# IrDA2TTLBoard.net
KiCad netlist of a schematic drawn in Altium Designer
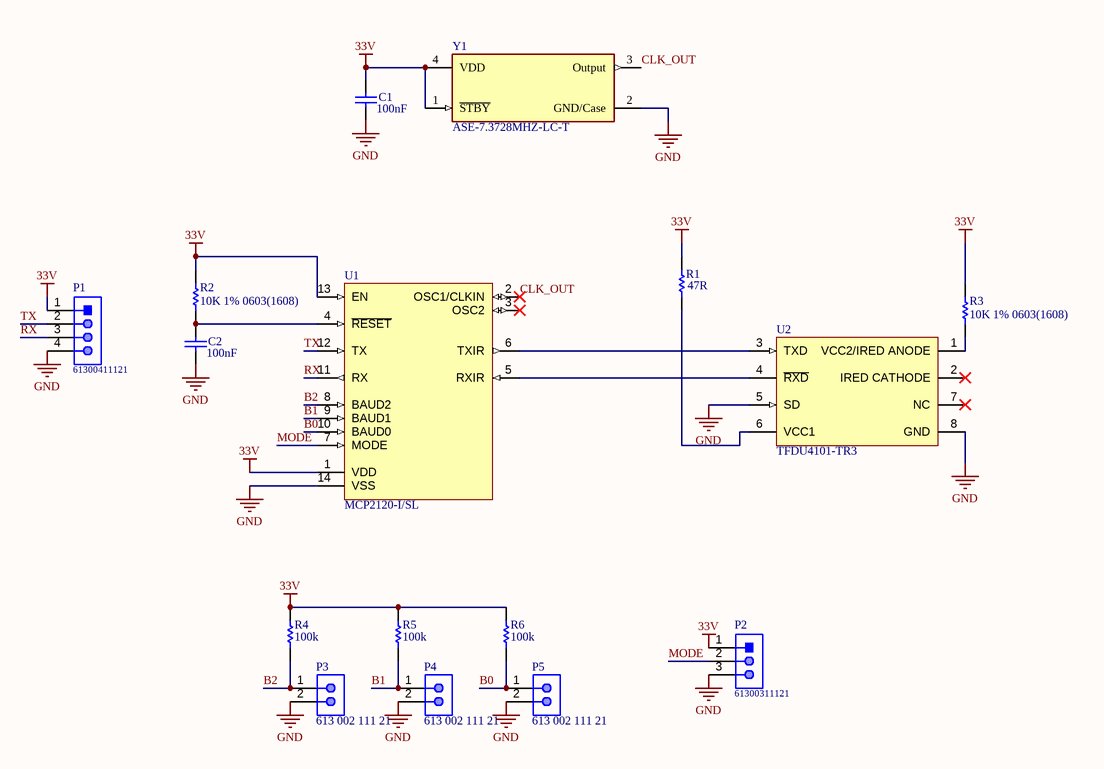
[diagram p0: IrDA2TTLBoard.SchDoc]

(export (version "E")
  (design (tool "Eeschema 10.0.6"))
  (components
    (comp (ref "C1")
      (value "100nF")
      (footprint "CAPC0603(1608)100_M")
      (description "CAP 100nF 6.3V ±10% 0603 (1608 Metric) Thickness 1mm SMD")
      (fields (field (name "TOLERANCE") "Â±10%") (field (name "Comment") "CAP 100nF 6.3V 0603(1608)"))
      (libsource (lib "Altium Content Vault") (part "CAP"))
    )
    (comp (ref "C2")
      (value "100nF")
      (footprint "CAPC0603(1608)100_M")
      (description "CAP 100nF 6.3V ±10% 0603 (1608 Metric) Thickness 1mm SMD")
      (fields (field (name "TOLERANCE") "Â±10%") (field (name "Comment") "CAP 100nF 6.3V 0603(1608)"))
      (libsource (lib "Altium Content Vault") (part "CAP"))
    )
    (comp (ref "P1")
      (value "61300411121")
      (footprint "61300411121")
      (description "THT Vertical Pin Header WR-PHD, Pitch 2.54 mm, Single Row, 4 pins")
      (fields (field (name "MANUFACTURER") "Wurth Elektronik") (field (name "PUBLISHER") "WurthElektronik"))
      (libsource (lib "Altium Content Vault") (part "WE-CN-1P-M-R4"))
    )
    (comp (ref "P2")
      (value "61300311121")
      (footprint "61300311121")
      (description "THT Vertical Pin Header WR-PHD, Pitch 2.54 mm, Single Row, 3 pins")
      (fields (field (name "MANUFACTURER") "Wurth Elektronik") (field (name "PUBLISHER") "WurthElektronik"))
      (libsource (lib "Altium Content Vault") (part "WE-CN-1P-M-R3"))
    )
    (comp (ref "P3")
      (value "613 002 111 21")
      (footprint "WE-61300211121_V")
      (libsource (lib "Altium Content Vault") (part "CN-1P-M-R2"))
    )
    (comp (ref "P4")
      (value "613 002 111 21")
      (footprint "WE-61300211121_V")
      (libsource (lib "Altium Content Vault") (part "CN-1P-M-R2"))
    )
    (comp (ref "P5")
      (value "613 002 111 21")
      (footprint "WE-61300211121_V")
      (libsource (lib "Altium Content Vault") (part "CN-1P-M-R2"))
    )
    (comp (ref "R1")
      (value "47R")
      (footprint "RESC1609X50X30LL10T20")
      (fields (field (name "MANUFACTURER") "Vishay Dale") (field (name "PART NUMBER") "CRCW060347R0FKEA"))
      (libsource (lib "Altium Content Vault") (part "RES"))
    )
    (comp (ref "R2")
      (value "10K 1% 0603(1608)")
      (footprint "RESC0603(1608)_N")
      (description "10K 0.1W 1% 0603 (1608 Metric)  SMD")
      (fields (field (name "POWER") "0.1 W") (field (name "TOLERANCE") "1 %"))
      (libsource (lib "Altium Content Vault") (part "RES"))
    )
    (comp (ref "R3")
      (value "10K 1% 0603(1608)")
      (footprint "RESC0603(1608)_N")
      (description "10K 0.1W 1% 0603 (1608 Metric)  SMD")
      (fields (field (name "POWER") "0.1 W") (field (name "TOLERANCE") "1 %"))
      (libsource (lib "Altium Content Vault") (part "RES"))
    )
    (comp (ref "R4")
      (value "100k")
      (footprint "RESC1609X50X30LL10T20")
      (fields (field (name "MANUFACTURER") "Vishay Dale") (field (name "PART NUMBER") "CRCW0603100KJNEA"))
      (libsource (lib "Altium Content Vault") (part "RES"))
    )
    (comp (ref "R5")
      (value "100k")
      (footprint "RESC1609X50X30LL10T20")
      (fields (field (name "MANUFACTURER") "Vishay Dale") (field (name "PART NUMBER") "CRCW0603100KJNEA"))
      (libsource (lib "Altium Content Vault") (part "RES"))
    )
    (comp (ref "R6")
      (value "100k")
      (footprint "RESC1609X50X30LL10T20")
      (fields (field (name "MANUFACTURER") "Vishay Dale") (field (name "PART NUMBER") "CRCW0603100KJNEA"))
      (libsource (lib "Altium Content Vault") (part "RES"))
    )
    (comp (ref "U1")
      (value "MCP2120-I/SL")
      (footprint "SOIC-SL14_N")
      (description "Infrared Encoder/Decoder, 14-Pin SOIC, Industrial Temperature")
      (libsource (lib "Altium Content Vault") (part "RF-CDC-MCP2120-14"))
    )
    (comp (ref "U2")
      (value "TFDU4101-TR3")
      (footprint "VISH-TFDU4100_4101-TR3_V")
      (fields (field (name "MANUFACTURER") "Vishay Semiconductor"))
      (libsource (lib "Altium Content Vault") (part "VISH-TFDU4101-8"))
    )
    (comp (ref "Y1")
      (value "ASE-7.3728MHZ-LC-T")
      (footprint "FP-ASE-MFG")
      (description "XTAL Oscillator 7.3728MHz ±50ppm CMOS 3.3V 4-SMD 3.2mm x 2.5mm")
      (libsource (lib "Altium Content Vault") (part "61a724e6190563596ac712fef61ad37"))
    )
  )
  (nets
    (net (code "1") (name "/B0") (class "Default")
      (node (ref "P5") (pin "1") (pinfunction "1_1") (pintype "passive"))
      (node (ref "R6") (pin "1") (pinfunction "1_1") (pintype "passive"))
      (node (ref "U1") (pin "10") (pinfunction "BAUD0_10") (pintype "input"))
    )
    (net (code "2") (name "/B1") (class "Default")
      (node (ref "P4") (pin "1") (pinfunction "1_1") (pintype "passive"))
      (node (ref "R5") (pin "1") (pinfunction "1_1") (pintype "passive"))
      (node (ref "U1") (pin "9") (pinfunction "BAUD1_9") (pintype "input"))
    )
    (net (code "3") (name "/B2") (class "Default")
      (node (ref "P3") (pin "1") (pinfunction "1_1") (pintype "passive"))
      (node (ref "R4") (pin "1") (pinfunction "1_1") (pintype "passive"))
      (node (ref "U1") (pin "8") (pinfunction "BAUD2_8") (pintype "input"))
    )
    (net (code "4") (name "/CLK_OUT") (class "Default")
      (node (ref "U1") (pin "2") (pinfunction "OSC1/CLKIN_2") (pintype "bidirectional"))
      (node (ref "Y1") (pin "3") (pinfunction "Output_3") (pintype "output"))
    )
    (net (code "5") (name "/MODE") (class "Default")
      (node (ref "P2") (pin "2") (pinfunction "2_2") (pintype "passive"))
      (node (ref "U1") (pin "7") (pinfunction "MODE_7") (pintype "input"))
    )
    (net (code "6") (name "/RX") (class "Default")
      (node (ref "P1") (pin "3") (pinfunction "3_3") (pintype "passive"))
      (node (ref "U1") (pin "11") (pinfunction "RX_11") (pintype "output"))
    )
    (net (code "7") (name "/TX") (class "Default")
      (node (ref "P1") (pin "2") (pinfunction "2_2") (pintype "passive"))
      (node (ref "U1") (pin "12") (pinfunction "TX_12") (pintype "input"))
    )
    (net (code "8") (name "33V") (class "Default")
      (node (ref "C1") (pin "2") (pinfunction "2_2") (pintype "passive"))
      (node (ref "P1") (pin "1") (pinfunction "1_1") (pintype "passive"))
      (node (ref "P2") (pin "1") (pinfunction "1_1") (pintype "passive"))
      (node (ref "R1") (pin "2") (pinfunction "2_2") (pintype "passive"))
      (node (ref "R2") (pin "2") (pinfunction "2_2") (pintype "passive"))
      (node (ref "R3") (pin "2") (pinfunction "2_2") (pintype "passive"))
      (node (ref "R4") (pin "2") (pinfunction "2_2") (pintype "passive"))
      (node (ref "R5") (pin "2") (pinfunction "2_2") (pintype "passive"))
      (node (ref "R6") (pin "2") (pinfunction "2_2") (pintype "passive"))
      (node (ref "U1") (pin "1") (pinfunction "VDD_1") (pintype "power_in"))
      (node (ref "U1") (pin "13") (pinfunction "EN_13") (pintype "input"))
      (node (ref "Y1") (pin "1") (pinfunction "~{STBY}_1") (pintype "input"))
      (node (ref "Y1") (pin "4") (pinfunction "VDD_4") (pintype "power_in"))
    )
    (net (code "9") (name "GND") (class "Default")
      (node (ref "C1") (pin "1") (pinfunction "1_1") (pintype "passive"))
      (node (ref "C2") (pin "1") (pinfunction "1_1") (pintype "passive"))
      (node (ref "P1") (pin "4") (pinfunction "4_4") (pintype "passive"))
      (node (ref "P2") (pin "3") (pinfunction "3_3") (pintype "passive"))
      (node (ref "P3") (pin "2") (pinfunction "2_2") (pintype "passive"))
      (node (ref "P4") (pin "2") (pinfunction "2_2") (pintype "passive"))
      (node (ref "P5") (pin "2") (pinfunction "2_2") (pintype "passive"))
      (node (ref "U1") (pin "14") (pinfunction "VSS_14") (pintype "power_in"))
      (node (ref "U2") (pin "5") (pinfunction "SD_5") (pintype "input"))
      (node (ref "U2") (pin "8") (pinfunction "GND_8") (pintype "power_in"))
      (node (ref "Y1") (pin "2") (pinfunction "GND/Case_2") (pintype "power_in"))
    )
    (net (code "10") (name "Net-(U1-RXIR)") (class "Default")
      (node (ref "U1") (pin "5") (pinfunction "RXIR_5") (pintype "input"))
      (node (ref "U2") (pin "4") (pinfunction "~{RXD}_4") (pintype "tri_state"))
    )
    (net (code "11") (name "Net-(U1-TXIR)") (class "Default")
      (node (ref "U1") (pin "6") (pinfunction "TXIR_6") (pintype "output"))
      (node (ref "U2") (pin "3") (pinfunction "TXD_3") (pintype "input"))
    )
    (net (code "12") (name "Net-(U1-~{RESET})") (class "Default")
      (node (ref "C2") (pin "2") (pinfunction "2_2") (pintype "passive"))
      (node (ref "R2") (pin "1") (pinfunction "1_1") (pintype "passive"))
      (node (ref "U1") (pin "4") (pinfunction "~{RESET}_4") (pintype "input"))
    )
    (net (code "13") (name "Net-(U2-VCC1)") (class "Default")
      (node (ref "R1") (pin "1") (pinfunction "1_1") (pintype "passive"))
      (node (ref "U2") (pin "6") (pinfunction "VCC1_6") (pintype "power_in"))
    )
    (net (code "14") (name "Net-(U2-VCC2{slash}IRED_ANODE)") (class "Default")
      (node (ref "R3") (pin "1") (pinfunction "1_1") (pintype "passive"))
      (node (ref "U2") (pin "1") (pinfunction "VCC2/IRED_ANODE_1") (pintype "power_in"))
    )
    (net (code "15") (name "unconnected-(U1-OSC2-Pad3)") (class "Default")
      (node (ref "U1") (pin "3") (pinfunction "OSC2_3") (pintype "bidirectional+no_connect"))
    )
    (net (code "16") (name "unconnected-(U2-IRED_CATHODE-Pad2)") (class "Default")
      (node (ref "U2") (pin "2") (pinfunction "IRED_CATHODE_2") (pintype "passive+no_connect"))
    )
    (net (code "17") (name "unconnected-(U2-NC-Pad7)") (class "Default")
      (node (ref "U2") (pin "7") (pinfunction "NC_7") (pintype "passive+no_connect"))
    )
  )
)
